# MoBa-Sicherungsverteiler_V100_2023-03-24.net
KiCad netlist of a schematic drawn in EAGLE
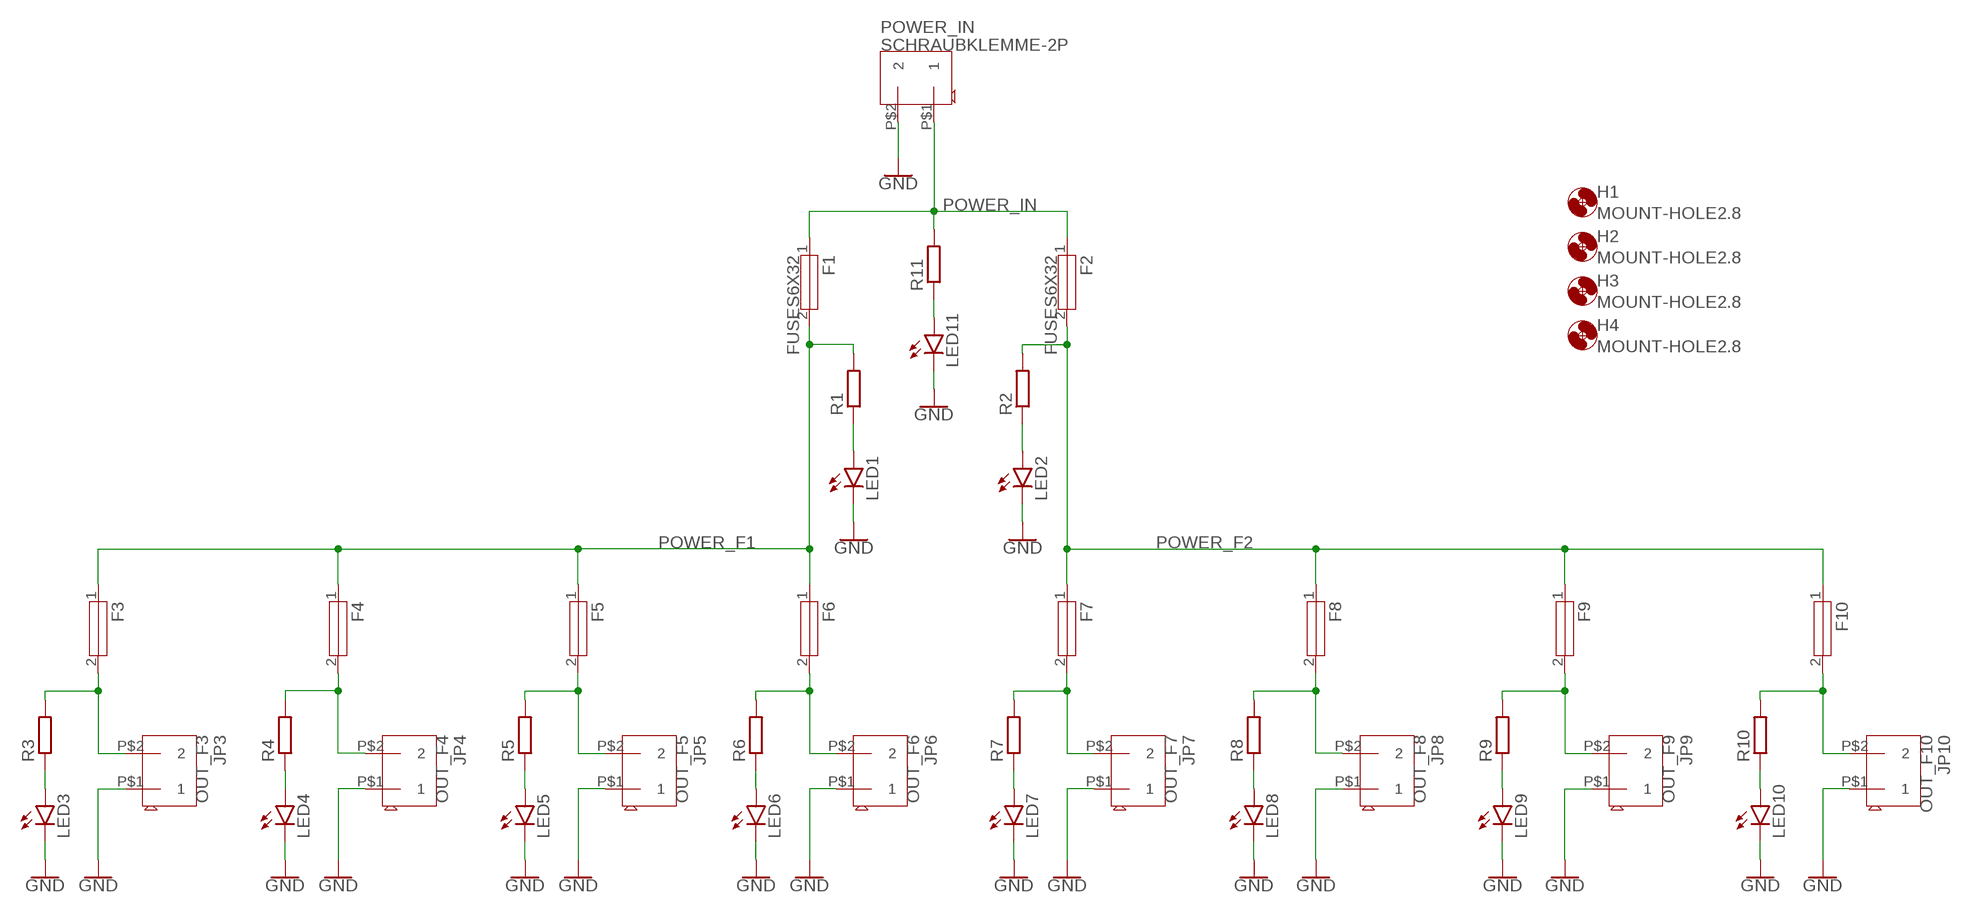
[diagram p0: schematic, sheet 1]

(export (version "E")
  (design (tool "Eeschema 10.0.6"))
  (components
    (comp (ref "F1")
      (value "FUSES6X32")
      (footprint "eagle-import:FUSE_6X32")
      (libsource (lib "eagle-import") (part "FUSES6X32"))
    )
    (comp (ref "F2")
      (value "FUSES6X32")
      (footprint "eagle-import:FUSE_6X32")
      (libsource (lib "eagle-import") (part "FUSES6X32"))
    )
    (comp (ref "F3")
      (value "FUSES5X20")
      (footprint "eagle-import:FUSE_5X20")
      (libsource (lib "eagle-import") (part "FUSES5X20"))
    )
    (comp (ref "F4")
      (value "FUSES5X20")
      (footprint "eagle-import:FUSE_5X20")
      (libsource (lib "eagle-import") (part "FUSES5X20"))
    )
    (comp (ref "F5")
      (value "FUSES5X20")
      (footprint "eagle-import:FUSE_5X20")
      (libsource (lib "eagle-import") (part "FUSES5X20"))
    )
    (comp (ref "F6")
      (value "FUSES5X20")
      (footprint "eagle-import:FUSE_5X20")
      (libsource (lib "eagle-import") (part "FUSES5X20"))
    )
    (comp (ref "F7")
      (value "FUSES5X20")
      (footprint "eagle-import:FUSE_5X20")
      (libsource (lib "eagle-import") (part "FUSES5X20"))
    )
    (comp (ref "F8")
      (value "FUSES5X20")
      (footprint "eagle-import:FUSE_5X20")
      (libsource (lib "eagle-import") (part "FUSES5X20"))
    )
    (comp (ref "F9")
      (value "FUSES5X20")
      (footprint "eagle-import:FUSE_5X20")
      (libsource (lib "eagle-import") (part "FUSES5X20"))
    )
    (comp (ref "F10")
      (value "FUSES5X20")
      (footprint "eagle-import:FUSE_5X20")
      (libsource (lib "eagle-import") (part "FUSES5X20"))
    )
    (comp (ref "H1")
      (value "MOUNT-HOLE2.8")
      (footprint "eagle-import:2,8")
      (libsource (lib "eagle-import") (part "MOUNT-HOLE2.8"))
    )
    (comp (ref "H2")
      (value "MOUNT-HOLE2.8")
      (footprint "eagle-import:2,8")
      (libsource (lib "eagle-import") (part "MOUNT-HOLE2.8"))
    )
    (comp (ref "H3")
      (value "MOUNT-HOLE2.8")
      (footprint "eagle-import:2,8")
      (libsource (lib "eagle-import") (part "MOUNT-HOLE2.8"))
    )
    (comp (ref "H4")
      (value "MOUNT-HOLE2.8")
      (footprint "eagle-import:2,8")
      (libsource (lib "eagle-import") (part "MOUNT-HOLE2.8"))
    )
    (comp (ref "JP3")
      (value "OUT_F3")
      (footprint "eagle-import:TERM-2P_508")
      (libsource (lib "eagle-import") (part "SCHRAUBKLEMME-2P"))
    )
    (comp (ref "JP4")
      (value "OUT_F4")
      (footprint "eagle-import:TERM-2P_508")
      (libsource (lib "eagle-import") (part "SCHRAUBKLEMME-2P"))
    )
    (comp (ref "JP5")
      (value "OUT_F5")
      (footprint "eagle-import:TERM-2P_508")
      (libsource (lib "eagle-import") (part "SCHRAUBKLEMME-2P"))
    )
    (comp (ref "JP6")
      (value "OUT_F6")
      (footprint "eagle-import:TERM-2P_508")
      (libsource (lib "eagle-import") (part "SCHRAUBKLEMME-2P"))
    )
    (comp (ref "JP7")
      (value "OUT_F7")
      (footprint "eagle-import:TERM-2P_508")
      (libsource (lib "eagle-import") (part "SCHRAUBKLEMME-2P"))
    )
    (comp (ref "JP8")
      (value "OUT_F8")
      (footprint "eagle-import:TERM-2P_508")
      (libsource (lib "eagle-import") (part "SCHRAUBKLEMME-2P"))
    )
    (comp (ref "JP9")
      (value "OUT_F9")
      (footprint "eagle-import:TERM-2P_508")
      (libsource (lib "eagle-import") (part "SCHRAUBKLEMME-2P"))
    )
    (comp (ref "JP10")
      (value "OUT_F10")
      (footprint "eagle-import:TERM-2P_508")
      (libsource (lib "eagle-import") (part "SCHRAUBKLEMME-2P"))
    )
    (comp (ref "LED1")
      (value "LED3MM")
      (footprint "eagle-import:LED3MM")
      (libsource (lib "eagle-import") (part "LED3MM"))
    )
    (comp (ref "LED2")
      (value "LED3MM")
      (footprint "eagle-import:LED3MM")
      (libsource (lib "eagle-import") (part "LED3MM"))
    )
    (comp (ref "LED3")
      (value "LED3MM")
      (footprint "eagle-import:LED3MM")
      (libsource (lib "eagle-import") (part "LED3MM"))
    )
    (comp (ref "LED4")
      (value "LED3MM")
      (footprint "eagle-import:LED3MM")
      (libsource (lib "eagle-import") (part "LED3MM"))
    )
    (comp (ref "LED5")
      (value "LED3MM")
      (footprint "eagle-import:LED3MM")
      (libsource (lib "eagle-import") (part "LED3MM"))
    )
    (comp (ref "LED6")
      (value "LED3MM")
      (footprint "eagle-import:LED3MM")
      (libsource (lib "eagle-import") (part "LED3MM"))
    )
    (comp (ref "LED7")
      (value "LED3MM")
      (footprint "eagle-import:LED3MM")
      (libsource (lib "eagle-import") (part "LED3MM"))
    )
    (comp (ref "LED8")
      (value "LED3MM")
      (footprint "eagle-import:LED3MM")
      (libsource (lib "eagle-import") (part "LED3MM"))
    )
    (comp (ref "LED9")
      (value "LED3MM")
      (footprint "eagle-import:LED3MM")
      (libsource (lib "eagle-import") (part "LED3MM"))
    )
    (comp (ref "LED10")
      (value "LED3MM")
      (footprint "eagle-import:LED3MM")
      (libsource (lib "eagle-import") (part "LED3MM"))
    )
    (comp (ref "LED11")
      (value "LED3MM")
      (footprint "eagle-import:LED3MM")
      (libsource (lib "eagle-import") (part "LED3MM"))
    )
    (comp (ref "POWER_IN")
      (value "SCHRAUBKLEMME-2P")
      (footprint "eagle-import:TERM-2P_508")
      (libsource (lib "eagle-import") (part "SCHRAUBKLEMME-2P"))
    )
    (comp (ref "R1")
      (value "R-EU_0207/10")
      (footprint "eagle-import:0207_10")
      (libsource (lib "eagle-import") (part "R-EU_0207/10"))
    )
    (comp (ref "R2")
      (value "R-EU_0207/10")
      (footprint "eagle-import:0207_10")
      (libsource (lib "eagle-import") (part "R-EU_0207/10"))
    )
    (comp (ref "R3")
      (value "R-EU_0207/10")
      (footprint "eagle-import:0207_10")
      (libsource (lib "eagle-import") (part "R-EU_0207/10"))
    )
    (comp (ref "R4")
      (value "R-EU_0207/10")
      (footprint "eagle-import:0207_10")
      (libsource (lib "eagle-import") (part "R-EU_0207/10"))
    )
    (comp (ref "R5")
      (value "R-EU_0207/10")
      (footprint "eagle-import:0207_10")
      (libsource (lib "eagle-import") (part "R-EU_0207/10"))
    )
    (comp (ref "R6")
      (value "R-EU_0207/10")
      (footprint "eagle-import:0207_10")
      (libsource (lib "eagle-import") (part "R-EU_0207/10"))
    )
    (comp (ref "R7")
      (value "R-EU_0207/10")
      (footprint "eagle-import:0207_10")
      (libsource (lib "eagle-import") (part "R-EU_0207/10"))
    )
    (comp (ref "R8")
      (value "R-EU_0207/10")
      (footprint "eagle-import:0207_10")
      (libsource (lib "eagle-import") (part "R-EU_0207/10"))
    )
    (comp (ref "R9")
      (value "R-EU_0207/10")
      (footprint "eagle-import:0207_10")
      (libsource (lib "eagle-import") (part "R-EU_0207/10"))
    )
    (comp (ref "R10")
      (value "R-EU_0207/10")
      (footprint "eagle-import:0207_10")
      (libsource (lib "eagle-import") (part "R-EU_0207/10"))
    )
    (comp (ref "R11")
      (value "R-EU_0207/10")
      (footprint "eagle-import:0207_10")
      (libsource (lib "eagle-import") (part "R-EU_0207/10"))
    )
  )
  (nets
    (net (code "1") (name "/POWER_F1") (class "Default")
      (node (ref "F1") (pin "2") (pinfunction "2_2") (pintype "bidirectional"))
      (node (ref "F3") (pin "1") (pinfunction "1_1") (pintype "bidirectional"))
      (node (ref "F4") (pin "1") (pinfunction "1_1") (pintype "bidirectional"))
      (node (ref "F5") (pin "1") (pinfunction "1_1") (pintype "bidirectional"))
      (node (ref "F6") (pin "1") (pinfunction "1_1") (pintype "bidirectional"))
      (node (ref "R1") (pin "2") (pinfunction "2_2") (pintype "passive"))
    )
    (net (code "2") (name "/POWER_F2") (class "Default")
      (node (ref "F10") (pin "1") (pinfunction "1_1") (pintype "bidirectional"))
      (node (ref "F2") (pin "2") (pinfunction "2_2") (pintype "bidirectional"))
      (node (ref "F7") (pin "1") (pinfunction "1_1") (pintype "bidirectional"))
      (node (ref "F8") (pin "1") (pinfunction "1_1") (pintype "bidirectional"))
      (node (ref "F9") (pin "1") (pinfunction "1_1") (pintype "bidirectional"))
      (node (ref "R2") (pin "2") (pinfunction "2_2") (pintype "passive"))
    )
    (net (code "3") (name "/POWER_IN") (class "Default")
      (node (ref "F1") (pin "1") (pinfunction "1_1") (pintype "bidirectional"))
      (node (ref "F2") (pin "1") (pinfunction "1_1") (pintype "bidirectional"))
      (node (ref "POWER_IN") (pin "P$1") (pinfunction "1_P$1") (pintype "bidirectional"))
      (node (ref "R11") (pin "2") (pinfunction "2_2") (pintype "passive"))
    )
    (net (code "4") (name "GND") (class "Default")
      (node (ref "JP10") (pin "P$1") (pinfunction "1_P$1") (pintype "bidirectional"))
      (node (ref "JP3") (pin "P$1") (pinfunction "1_P$1") (pintype "bidirectional"))
      (node (ref "JP4") (pin "P$1") (pinfunction "1_P$1") (pintype "bidirectional"))
      (node (ref "JP5") (pin "P$1") (pinfunction "1_P$1") (pintype "bidirectional"))
      (node (ref "JP6") (pin "P$1") (pinfunction "1_P$1") (pintype "bidirectional"))
      (node (ref "JP7") (pin "P$1") (pinfunction "1_P$1") (pintype "bidirectional"))
      (node (ref "JP8") (pin "P$1") (pinfunction "1_P$1") (pintype "bidirectional"))
      (node (ref "JP9") (pin "P$1") (pinfunction "1_P$1") (pintype "bidirectional"))
      (node (ref "LED1") (pin "K") (pinfunction "C_K") (pintype "passive"))
      (node (ref "LED10") (pin "K") (pinfunction "C_K") (pintype "passive"))
      (node (ref "LED11") (pin "K") (pinfunction "C_K") (pintype "passive"))
      (node (ref "LED2") (pin "K") (pinfunction "C_K") (pintype "passive"))
      (node (ref "LED3") (pin "K") (pinfunction "C_K") (pintype "passive"))
      (node (ref "LED4") (pin "K") (pinfunction "C_K") (pintype "passive"))
      (node (ref "LED5") (pin "K") (pinfunction "C_K") (pintype "passive"))
      (node (ref "LED6") (pin "K") (pinfunction "C_K") (pintype "passive"))
      (node (ref "LED7") (pin "K") (pinfunction "C_K") (pintype "passive"))
      (node (ref "LED8") (pin "K") (pinfunction "C_K") (pintype "passive"))
      (node (ref "LED9") (pin "K") (pinfunction "C_K") (pintype "passive"))
      (node (ref "POWER_IN") (pin "P$2") (pinfunction "2_P$2") (pintype "bidirectional"))
    )
    (net (code "5") (name "Net-(JP3-2)") (class "Default")
      (node (ref "F3") (pin "2") (pinfunction "2_2") (pintype "bidirectional"))
      (node (ref "JP3") (pin "P$2") (pinfunction "2_P$2") (pintype "bidirectional"))
      (node (ref "R3") (pin "2") (pinfunction "2_2") (pintype "passive"))
    )
    (net (code "6") (name "Net-(JP4-2)") (class "Default")
      (node (ref "F4") (pin "2") (pinfunction "2_2") (pintype "bidirectional"))
      (node (ref "JP4") (pin "P$2") (pinfunction "2_P$2") (pintype "bidirectional"))
      (node (ref "R4") (pin "2") (pinfunction "2_2") (pintype "passive"))
    )
    (net (code "7") (name "Net-(JP5-2)") (class "Default")
      (node (ref "F5") (pin "2") (pinfunction "2_2") (pintype "bidirectional"))
      (node (ref "JP5") (pin "P$2") (pinfunction "2_P$2") (pintype "bidirectional"))
      (node (ref "R5") (pin "2") (pinfunction "2_2") (pintype "passive"))
    )
    (net (code "8") (name "Net-(JP6-2)") (class "Default")
      (node (ref "F6") (pin "2") (pinfunction "2_2") (pintype "bidirectional"))
      (node (ref "JP6") (pin "P$2") (pinfunction "2_P$2") (pintype "bidirectional"))
      (node (ref "R6") (pin "2") (pinfunction "2_2") (pintype "passive"))
    )
    (net (code "9") (name "Net-(JP7-2)") (class "Default")
      (node (ref "F7") (pin "2") (pinfunction "2_2") (pintype "bidirectional"))
      (node (ref "JP7") (pin "P$2") (pinfunction "2_P$2") (pintype "bidirectional"))
      (node (ref "R7") (pin "2") (pinfunction "2_2") (pintype "passive"))
    )
    (net (code "10") (name "Net-(JP8-2)") (class "Default")
      (node (ref "F8") (pin "2") (pinfunction "2_2") (pintype "bidirectional"))
      (node (ref "JP8") (pin "P$2") (pinfunction "2_P$2") (pintype "bidirectional"))
      (node (ref "R8") (pin "2") (pinfunction "2_2") (pintype "passive"))
    )
    (net (code "11") (name "Net-(JP9-2)") (class "Default")
      (node (ref "F9") (pin "2") (pinfunction "2_2") (pintype "bidirectional"))
      (node (ref "JP9") (pin "P$2") (pinfunction "2_P$2") (pintype "bidirectional"))
      (node (ref "R9") (pin "2") (pinfunction "2_2") (pintype "passive"))
    )
    (net (code "12") (name "Net-(JP10-2)") (class "Default")
      (node (ref "F10") (pin "2") (pinfunction "2_2") (pintype "bidirectional"))
      (node (ref "JP10") (pin "P$2") (pinfunction "2_P$2") (pintype "bidirectional"))
      (node (ref "R10") (pin "2") (pinfunction "2_2") (pintype "passive"))
    )
    (net (code "13") (name "Net-(LED1-PadA)") (class "Default")
      (node (ref "LED1") (pin "A") (pinfunction "A_A") (pintype "passive"))
      (node (ref "R1") (pin "1") (pinfunction "1_1") (pintype "passive"))
    )
    (net (code "14") (name "Net-(LED2-PadA)") (class "Default")
      (node (ref "LED2") (pin "A") (pinfunction "A_A") (pintype "passive"))
      (node (ref "R2") (pin "1") (pinfunction "1_1") (pintype "passive"))
    )
    (net (code "15") (name "Net-(LED3-PadA)") (class "Default")
      (node (ref "LED3") (pin "A") (pinfunction "A_A") (pintype "passive"))
      (node (ref "R3") (pin "1") (pinfunction "1_1") (pintype "passive"))
    )
    (net (code "16") (name "Net-(LED4-PadA)") (class "Default")
      (node (ref "LED4") (pin "A") (pinfunction "A_A") (pintype "passive"))
      (node (ref "R4") (pin "1") (pinfunction "1_1") (pintype "passive"))
    )
    (net (code "17") (name "Net-(LED5-PadA)") (class "Default")
      (node (ref "LED5") (pin "A") (pinfunction "A_A") (pintype "passive"))
      (node (ref "R5") (pin "1") (pinfunction "1_1") (pintype "passive"))
    )
    (net (code "18") (name "Net-(LED6-PadA)") (class "Default")
      (node (ref "LED6") (pin "A") (pinfunction "A_A") (pintype "passive"))
      (node (ref "R6") (pin "1") (pinfunction "1_1") (pintype "passive"))
    )
    (net (code "19") (name "Net-(LED7-PadA)") (class "Default")
      (node (ref "LED7") (pin "A") (pinfunction "A_A") (pintype "passive"))
      (node (ref "R7") (pin "1") (pinfunction "1_1") (pintype "passive"))
    )
    (net (code "20") (name "Net-(LED8-PadA)") (class "Default")
      (node (ref "LED8") (pin "A") (pinfunction "A_A") (pintype "passive"))
      (node (ref "R8") (pin "1") (pinfunction "1_1") (pintype "passive"))
    )
    (net (code "21") (name "Net-(LED9-PadA)") (class "Default")
      (node (ref "LED9") (pin "A") (pinfunction "A_A") (pintype "passive"))
      (node (ref "R9") (pin "1") (pinfunction "1_1") (pintype "passive"))
    )
    (net (code "22") (name "Net-(LED10-PadA)") (class "Default")
      (node (ref "LED10") (pin "A") (pinfunction "A_A") (pintype "passive"))
      (node (ref "R10") (pin "1") (pinfunction "1_1") (pintype "passive"))
    )
    (net (code "23") (name "Net-(LED11-PadA)") (class "Default")
      (node (ref "LED11") (pin "A") (pinfunction "A_A") (pintype "passive"))
      (node (ref "R11") (pin "1") (pinfunction "1_1") (pintype "passive"))
    )
  )
)
